# qstp_q5.net
KiCad netlist of a schematic drawn in EAGLE
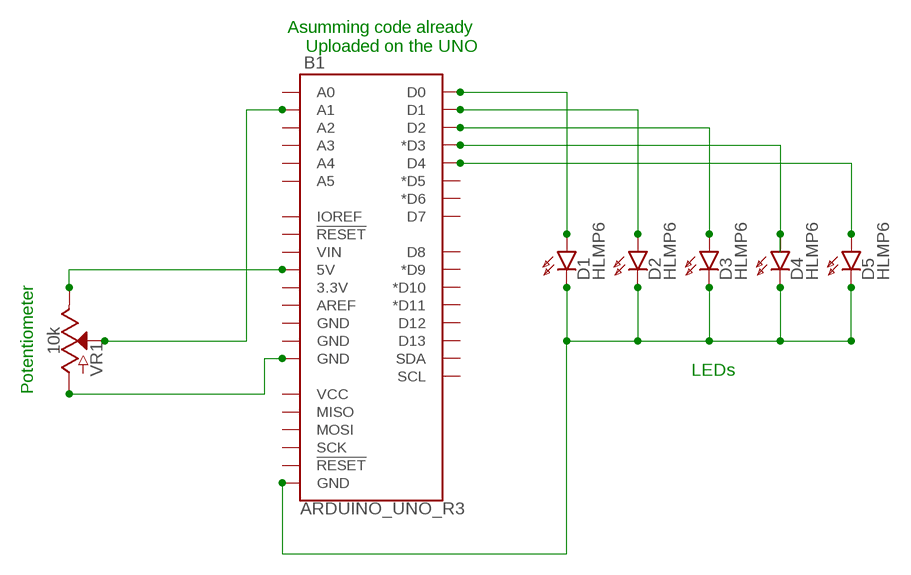
[diagram p0: schematic, sheet 1]

(export (version "E")
  (design (tool "Eeschema 10.0.6"))
  (components
    (comp (ref "B1")
      (value "ARDUINO_UNO_R3")
      (footprint "eagle-import:ARDUINO_R3")
      (libsource (lib "eagle-import") (part "ARDUINO_UNO_R3"))
    )
    (comp (ref "D1")
      (value "HLMP6")
      (footprint "eagle-import:HLMP6")
      (fields (field (name "MF") "AGILENT TECHNOLOGIES") (field (name "MPN") "HLMP-6500"))
      (libsource (lib "eagle-import") (part "HLMP6"))
    )
    (comp (ref "D2")
      (value "HLMP6")
      (footprint "eagle-import:HLMP6")
      (fields (field (name "MF") "AGILENT TECHNOLOGIES") (field (name "MPN") "HLMP-6500"))
      (libsource (lib "eagle-import") (part "HLMP6"))
    )
    (comp (ref "D3")
      (value "HLMP6")
      (footprint "eagle-import:HLMP6")
      (fields (field (name "MF") "AGILENT TECHNOLOGIES") (field (name "MPN") "HLMP-6500"))
      (libsource (lib "eagle-import") (part "HLMP6"))
    )
    (comp (ref "D4")
      (value "HLMP6")
      (footprint "eagle-import:HLMP6")
      (fields (field (name "MF") "AGILENT TECHNOLOGIES") (field (name "MPN") "HLMP-6500"))
      (libsource (lib "eagle-import") (part "HLMP6"))
    )
    (comp (ref "D5")
      (value "HLMP6")
      (footprint "eagle-import:HLMP6")
      (fields (field (name "MF") "AGILENT TECHNOLOGIES") (field (name "MPN") "HLMP-6500"))
      (libsource (lib "eagle-import") (part "HLMP6"))
    )
    (comp (ref "VR1")
      (value "10k")
      (footprint "eagle-import:POT-PTH-ALPS")
      (libsource (lib "eagle-import") (part "POTENTIOMETER-PTH-9MM-1/20W-20%"))
    )
  )
  (nets
    (net (code "1") (name "Net-(B1-*D3)") (class "Default")
      (node (ref "B1") (pin "D3") (pinfunction "*D3_D3") (pintype "bidirectional"))
      (node (ref "D4") (pin "A") (pinfunction "A_A") (pintype "passive"))
    )
    (net (code "2") (name "Net-(B1-GND-PadGND@1)") (class "Default")
      (node (ref "B1") (pin "GND@1") (pinfunction "GND_GND@1") (pintype "bidirectional"))
      (node (ref "D1") (pin "K") (pinfunction "K_K") (pintype "passive"))
      (node (ref "D2") (pin "K") (pinfunction "K_K") (pintype "passive"))
      (node (ref "D3") (pin "K") (pinfunction "K_K") (pintype "passive"))
      (node (ref "D4") (pin "K") (pinfunction "K_K") (pintype "passive"))
      (node (ref "D5") (pin "K") (pinfunction "K_K") (pintype "passive"))
    )
    (net (code "3") (name "Net-(B1-PadD0)") (class "Default")
      (node (ref "B1") (pin "D0") (pinfunction "D0_D0") (pintype "bidirectional"))
      (node (ref "D1") (pin "A") (pinfunction "A_A") (pintype "passive"))
    )
    (net (code "4") (name "Net-(B1-PadD1)") (class "Default")
      (node (ref "B1") (pin "D1") (pinfunction "D1_D1") (pintype "bidirectional"))
      (node (ref "D2") (pin "A") (pinfunction "A_A") (pintype "passive"))
    )
    (net (code "5") (name "Net-(B1-PadD2)") (class "Default")
      (node (ref "B1") (pin "D2") (pinfunction "D2_D2") (pintype "bidirectional"))
      (node (ref "D3") (pin "A") (pinfunction "A_A") (pintype "passive"))
    )
    (net (code "6") (name "Net-(B1-PadD4)") (class "Default")
      (node (ref "B1") (pin "D4") (pinfunction "D4_D4") (pintype "bidirectional"))
      (node (ref "D5") (pin "A") (pinfunction "A_A") (pintype "passive"))
    )
    (net (code "7") (name "Net-(VR1-A)") (class "Default")
      (node (ref "B1") (pin "GND@2") (pinfunction "GND_GND@2") (pintype "bidirectional"))
      (node (ref "VR1") (pin "P$3") (pinfunction "A_P$3") (pintype "passive"))
    )
    (net (code "8") (name "Net-(VR1-E)") (class "Default")
      (node (ref "B1") (pin "5V") (pinfunction "5V_5V") (pintype "bidirectional"))
      (node (ref "VR1") (pin "P$1") (pinfunction "E_P$1") (pintype "passive"))
    )
    (net (code "9") (name "Net-(VR1-S)") (class "Default")
      (node (ref "B1") (pin "A1") (pinfunction "A1_A1") (pintype "bidirectional"))
      (node (ref "VR1") (pin "P$2") (pinfunction "S_P$2") (pintype "passive"))
    )
    (net (code "10") (name "unconnected-(B1-*D5-PadD5)") (class "Default")
      (node (ref "B1") (pin "D5") (pinfunction "*D5_D5") (pintype "bidirectional"))
    )
    (net (code "11") (name "unconnected-(B1-*D6-PadD6)") (class "Default")
      (node (ref "B1") (pin "D6") (pinfunction "*D6_D6") (pintype "bidirectional"))
    )
    (net (code "12") (name "unconnected-(B1-*D9-PadD9)") (class "Default")
      (node (ref "B1") (pin "D9") (pinfunction "*D9_D9") (pintype "bidirectional"))
    )
    (net (code "13") (name "unconnected-(B1-*D10-PadD10)") (class "Default")
      (node (ref "B1") (pin "D10") (pinfunction "*D10_D10") (pintype "bidirectional"))
    )
    (net (code "14") (name "unconnected-(B1-*D11-PadD11)") (class "Default")
      (node (ref "B1") (pin "D11") (pinfunction "*D11_D11") (pintype "bidirectional"))
    )
    (net (code "15") (name "unconnected-(B1-GND-PadGND@3)") (class "Default")
      (node (ref "B1") (pin "GND@3") (pinfunction "GND_GND@3") (pintype "bidirectional"))
    )
    (net (code "16") (name "unconnected-(B1-GND-PadGND@4)") (class "Default")
      (node (ref "B1") (pin "GND@4") (pinfunction "GND_GND@4") (pintype "bidirectional"))
    )
    (net (code "17") (name "unconnected-(B1-Pad3.3V)") (class "Default")
      (node (ref "B1") (pin "3.3V") (pinfunction "3.3V_3.3V") (pintype "bidirectional"))
    )
    (net (code "18") (name "unconnected-(B1-PadA0)") (class "Default")
      (node (ref "B1") (pin "A0") (pinfunction "A0_A0") (pintype "bidirectional"))
    )
    (net (code "19") (name "unconnected-(B1-PadA2)") (class "Default")
      (node (ref "B1") (pin "A2") (pinfunction "A2_A2") (pintype "bidirectional"))
    )
    (net (code "20") (name "unconnected-(B1-PadA3)") (class "Default")
      (node (ref "B1") (pin "A3") (pinfunction "A3_A3") (pintype "bidirectional"))
    )
    (net (code "21") (name "unconnected-(B1-PadA4)") (class "Default")
      (node (ref "B1") (pin "A4") (pinfunction "A4_A4") (pintype "bidirectional"))
    )
    (net (code "22") (name "unconnected-(B1-PadA5)") (class "Default")
      (node (ref "B1") (pin "A5") (pinfunction "A5_A5") (pintype "bidirectional"))
    )
    (net (code "23") (name "unconnected-(B1-PadAREF)") (class "Default")
      (node (ref "B1") (pin "AREF") (pinfunction "AREF_AREF") (pintype "bidirectional"))
    )
    (net (code "24") (name "unconnected-(B1-PadD7)") (class "Default")
      (node (ref "B1") (pin "D7") (pinfunction "D7_D7") (pintype "bidirectional"))
    )
    (net (code "25") (name "unconnected-(B1-PadD8)") (class "Default")
      (node (ref "B1") (pin "D8") (pinfunction "D8_D8") (pintype "bidirectional"))
    )
    (net (code "26") (name "unconnected-(B1-PadD12)") (class "Default")
      (node (ref "B1") (pin "D12") (pinfunction "D12_D12") (pintype "bidirectional"))
    )
    (net (code "27") (name "unconnected-(B1-PadD13)") (class "Default")
      (node (ref "B1") (pin "D13") (pinfunction "D13_D13") (pintype "bidirectional"))
    )
    (net (code "28") (name "unconnected-(B1-PadIOREF)") (class "Default")
      (node (ref "B1") (pin "IOREF") (pinfunction "IOREF_IOREF") (pintype "bidirectional"))
    )
    (net (code "29") (name "unconnected-(B1-PadMISO)") (class "Default")
      (node (ref "B1") (pin "MISO") (pinfunction "MISO_MISO") (pintype "bidirectional"))
    )
    (net (code "30") (name "unconnected-(B1-PadMOSI)") (class "Default")
      (node (ref "B1") (pin "MOSI") (pinfunction "MOSI_MOSI") (pintype "bidirectional"))
    )
    (net (code "31") (name "unconnected-(B1-PadSCK)") (class "Default")
      (node (ref "B1") (pin "SCK") (pinfunction "SCK_SCK") (pintype "bidirectional"))
    )
    (net (code "32") (name "unconnected-(B1-PadSCL)") (class "Default")
      (node (ref "B1") (pin "SCL") (pinfunction "SCL_SCL") (pintype "bidirectional"))
    )
    (net (code "33") (name "unconnected-(B1-PadSDA)") (class "Default")
      (node (ref "B1") (pin "SDA") (pinfunction "SDA_SDA") (pintype "bidirectional"))
    )
    (net (code "34") (name "unconnected-(B1-PadVCC)") (class "Default")
      (node (ref "B1") (pin "VCC") (pinfunction "VCC_VCC") (pintype "bidirectional"))
    )
    (net (code "35") (name "unconnected-(B1-PadVIN)") (class "Default")
      (node (ref "B1") (pin "VIN") (pinfunction "VIN_VIN") (pintype "bidirectional"))
    )
    (net (code "36") (name "unconnected-(B1-~{RESET}-PadRESET@1)") (class "Default")
      (node (ref "B1") (pin "RESET@1") (pinfunction "~{RESET}_RESET@1") (pintype "bidirectional"))
    )
    (net (code "37") (name "unconnected-(B1-~{RESET}-PadRESET@2)") (class "Default")
      (node (ref "B1") (pin "RESET@2") (pinfunction "~{RESET}_RESET@2") (pintype "bidirectional"))
    )
  )
)
